# CMD_Light.net
KiCad netlist of a schematic drawn in EAGLE
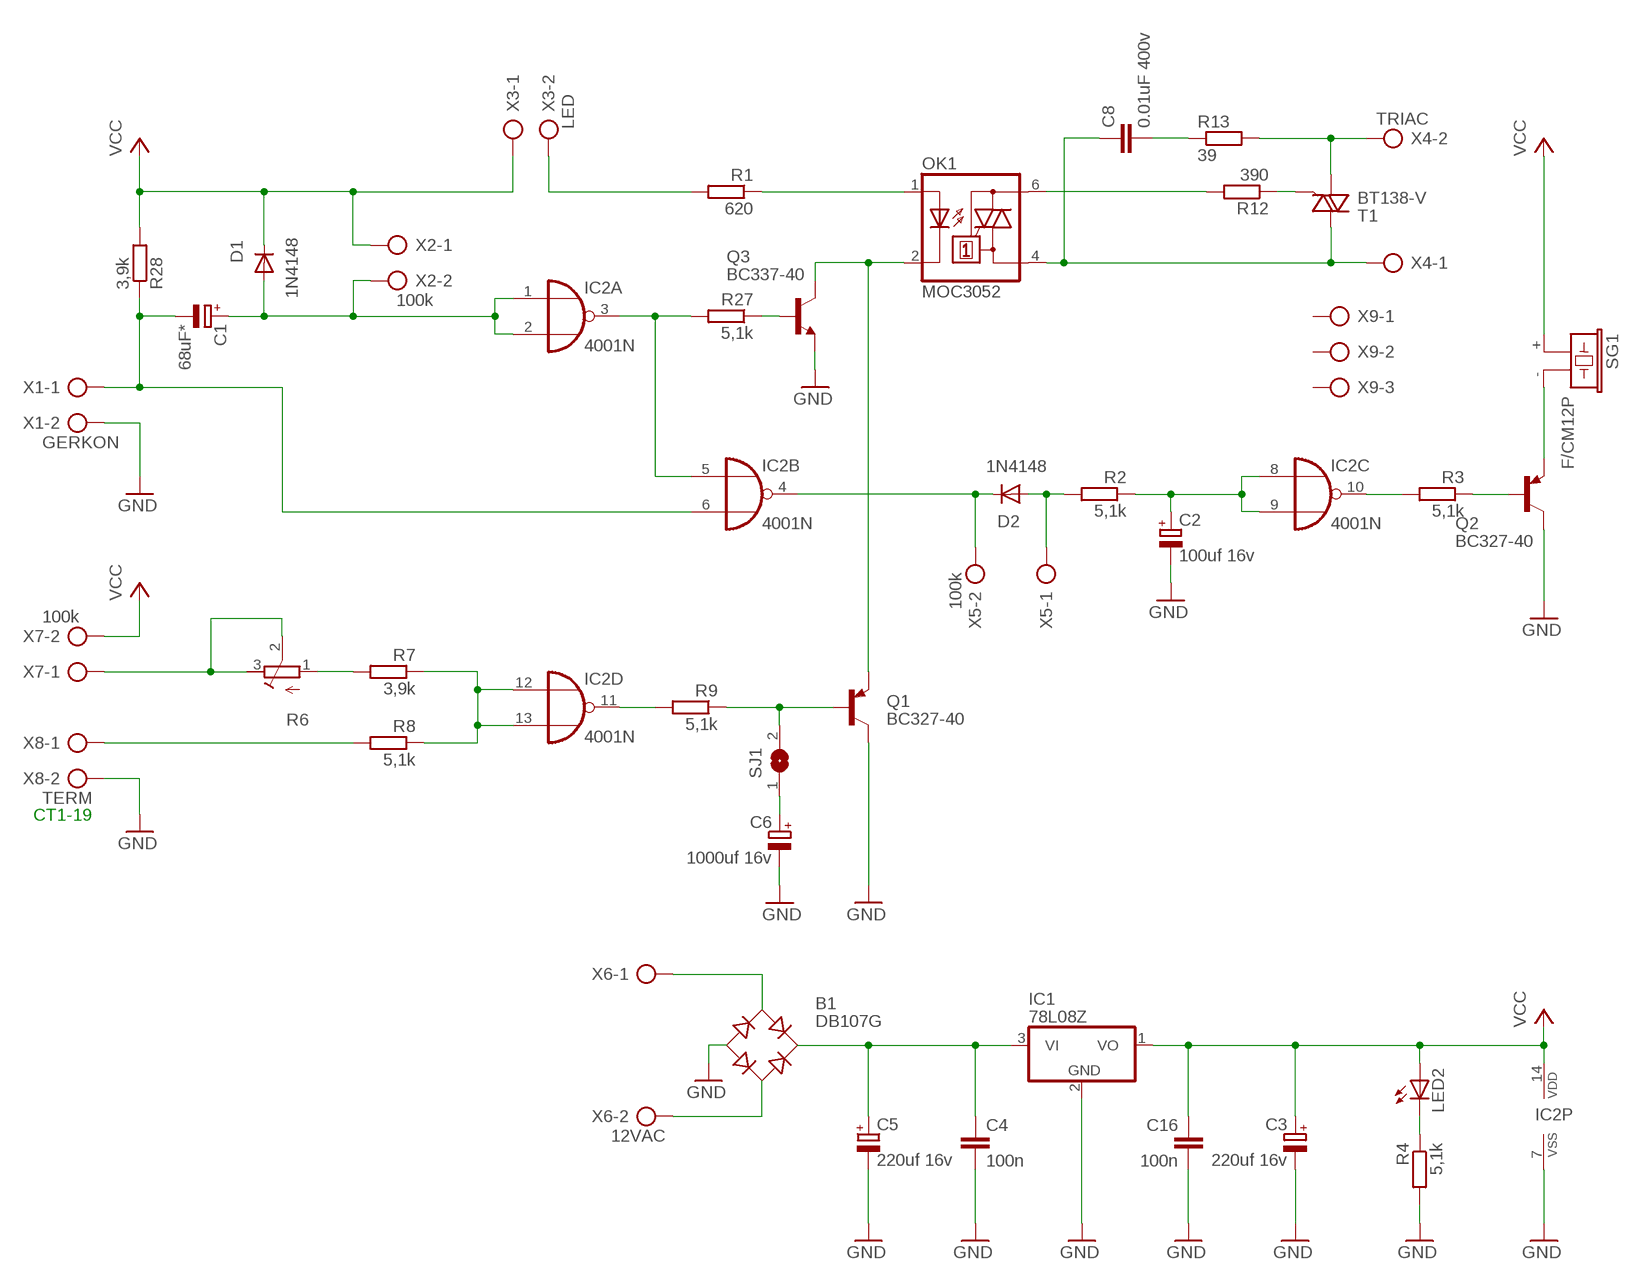
[diagram p0: schematic, sheet 1]

(export (version "E")
  (design (tool "Eeschema 10.0.6"))
  (components
    (comp (ref "B1")
      (value "DB107G")
      (footprint "eagle-import:DB")
      (libsource (lib "eagle-import") (part "DB?GDB107"))
    )
    (comp (ref "C1")
      (value "68uF*")
      (footprint "eagle-import:E3,5-8")
      (libsource (lib "eagle-import") (part "CPOL-EUE3.5-8"))
    )
    (comp (ref "C2")
      (value "100uf 16v")
      (footprint "eagle-import:E3,5-8")
      (libsource (lib "eagle-import") (part "CPOL-EUE3.5-8"))
    )
    (comp (ref "C3")
      (value "220uf 16v")
      (footprint "eagle-import:E3,5-8")
      (libsource (lib "eagle-import") (part "CPOL-EUE3.5-8"))
    )
    (comp (ref "C4")
      (value "100n")
      (footprint "eagle-import:C050-035X075")
      (libsource (lib "eagle-import") (part "C-EU050-035X075"))
    )
    (comp (ref "C5")
      (value "220uf 16v")
      (footprint "eagle-import:E3,5-8")
      (libsource (lib "eagle-import") (part "CPOL-EUE3.5-8"))
    )
    (comp (ref "C6")
      (value "1000uf 16v")
      (footprint "eagle-import:E5-10,5")
      (libsource (lib "eagle-import") (part "CPOL-EUE5-10.5"))
    )
    (comp (ref "C8")
      (value "0.01uF 400v")
      (footprint "eagle-import:C075-063X106")
      (libsource (lib "eagle-import") (part "C-EU075-063X106"))
    )
    (comp (ref "C16")
      (value "100n")
      (footprint "eagle-import:C050-035X075")
      (libsource (lib "eagle-import") (part "C-EU050-035X075"))
    )
    (comp (ref "D1")
      (value "1N4148")
      (footprint "eagle-import:DO41-8")
      (libsource (lib "eagle-import") (part "1N4004_"))
    )
    (comp (ref "D2")
      (value "1N4148")
      (footprint "eagle-import:DO41-10")
      (libsource (lib "eagle-import") (part "1N4004"))
    )
    (comp (ref "IC1")
      (value "78L08Z")
      (footprint "eagle-import:TO92")
      (libsource (lib "eagle-import") (part "78ZL08"))
    )
    (comp (ref "IC2")
      (value "4001N")
      (footprint "eagle-import:DIL14")
      (libsource (lib "eagle-import") (part "4001N"))
    )
    (comp (ref "LED2")
      (value "LED3MM")
      (footprint "eagle-import:LED3MM")
      (libsource (lib "eagle-import") (part "LED3MM"))
    )
    (comp (ref "OK1")
      (value "MOC3052")
      (footprint "eagle-import:DIL06")
      (fields (field (name "MF") "FAIRCHILD SEMICONDUCTOR") (field (name "MPN") "MOC3042-M"))
      (libsource (lib "eagle-import") (part "MOC3042M"))
    )
    (comp (ref "Q1")
      (value "BC327-40")
      (footprint "eagle-import:TO92-EBC")
      (libsource (lib "eagle-import") (part "BC327-40"))
    )
    (comp (ref "Q2")
      (value "BC327-40")
      (footprint "eagle-import:TO92-EBC")
      (libsource (lib "eagle-import") (part "BC327-40"))
    )
    (comp (ref "Q3")
      (value "BC337-40")
      (footprint "eagle-import:TO92-EBC")
      (libsource (lib "eagle-import") (part "BC338-40"))
    )
    (comp (ref "R1")
      (value "620")
      (footprint "eagle-import:0207_10")
      (libsource (lib "eagle-import") (part "R-EU_0207/10"))
    )
    (comp (ref "R2")
      (value "5,1k")
      (footprint "eagle-import:0207_10")
      (libsource (lib "eagle-import") (part "R-EU_0207/10"))
    )
    (comp (ref "R3")
      (value "5,1k")
      (footprint "eagle-import:0207_10")
      (libsource (lib "eagle-import") (part "R-EU_0207/10"))
    )
    (comp (ref "R4")
      (value "5,1k")
      (footprint "eagle-import:0207_10")
      (libsource (lib "eagle-import") (part "R-EU_0207/10"))
    )
    (comp (ref "R6")
      (value "R-TRIMM3339P")
      (footprint "eagle-import:RTRIM3339P")
      (libsource (lib "eagle-import") (part "R-TRIMM3339P"))
    )
    (comp (ref "R7")
      (value "3,9k")
      (footprint "eagle-import:0207_10")
      (libsource (lib "eagle-import") (part "R-EU_0207/10"))
    )
    (comp (ref "R8")
      (value "5,1k")
      (footprint "eagle-import:0207_10")
      (libsource (lib "eagle-import") (part "R-EU_0207/10"))
    )
    (comp (ref "R9")
      (value "5,1k")
      (footprint "eagle-import:0207_10")
      (libsource (lib "eagle-import") (part "R-EU_0207/10"))
    )
    (comp (ref "R12")
      (value "390")
      (footprint "eagle-import:0207_10")
      (libsource (lib "eagle-import") (part "R-EU_0207/10"))
    )
    (comp (ref "R13")
      (value "39")
      (footprint "eagle-import:0411_12")
      (libsource (lib "eagle-import") (part "R-EU_0411/12"))
    )
    (comp (ref "R27")
      (value "5,1k")
      (footprint "eagle-import:0207_10")
      (libsource (lib "eagle-import") (part "R-EU_0207/10"))
    )
    (comp (ref "R28")
      (value "3,9k")
      (footprint "eagle-import:0207_12")
      (libsource (lib "eagle-import") (part "R-EU_0207/12"))
    )
    (comp (ref "SG1")
      (value "F/CM12P")
      (footprint "eagle-import:F_CM12P")
      (libsource (lib "eagle-import") (part "F/CM12P"))
    )
    (comp (ref "SJ1") (value "SJ") (footprint "eagle-import:SJ") (libsource (lib "eagle-import") (part "SJ")))
    (comp (ref "T1")
      (value "BT138-V")
      (footprint "eagle-import:TO220BV")
      (libsource (lib "eagle-import") (part "BT138-V"))
    )
    (comp (ref "X1")
      (value "GERKON")
      (footprint "eagle-import:AK500_2")
      (libsource (lib "eagle-import") (part "AK500/2"))
    )
    (comp (ref "X2")
      (value "100k")
      (footprint "eagle-import:AK500_2")
      (libsource (lib "eagle-import") (part "AK500/2"))
    )
    (comp (ref "X3")
      (value "LED")
      (footprint "eagle-import:AK500_2")
      (libsource (lib "eagle-import") (part "AK500/2"))
    )
    (comp (ref "X4")
      (value "TRIAC")
      (footprint "eagle-import:AK500_2")
      (libsource (lib "eagle-import") (part "AK500/2"))
    )
    (comp (ref "X5")
      (value "100k")
      (footprint "eagle-import:AK500_2")
      (libsource (lib "eagle-import") (part "AK500/2"))
    )
    (comp (ref "X6")
      (value "12VAC")
      (footprint "eagle-import:AK500_2")
      (libsource (lib "eagle-import") (part "AK500/2"))
    )
    (comp (ref "X7")
      (value "100k")
      (footprint "eagle-import:AK500_2")
      (libsource (lib "eagle-import") (part "AK500/2"))
    )
    (comp (ref "X8")
      (value "TERM")
      (footprint "eagle-import:AK500_2")
      (libsource (lib "eagle-import") (part "AK500/2"))
    )
    (comp (ref "X9")
      (value "AK500/3")
      (footprint "eagle-import:AK500_3")
      (libsource (lib "eagle-import") (part "AK500/3"))
    )
  )
  (nets
    (net (code "1") (name "GND") (class "Default")
      (node (ref "B1") (pin "-") (pinfunction "-_-") (pintype "passive"))
      (node (ref "C16") (pin "2") (pinfunction "2_2") (pintype "passive"))
      (node (ref "C2") (pin "-") (pinfunction "-_-") (pintype "passive"))
      (node (ref "C3") (pin "-") (pinfunction "-_-") (pintype "passive"))
      (node (ref "C4") (pin "2") (pinfunction "2_2") (pintype "passive"))
      (node (ref "C5") (pin "-") (pinfunction "-_-") (pintype "passive"))
      (node (ref "C6") (pin "-") (pinfunction "-_-") (pintype "passive"))
      (node (ref "IC1") (pin "2") (pinfunction "GND_2") (pintype "passive"))
      (node (ref "IC2") (pin "7") (pinfunction "VSS_7") (pintype "power_in"))
      (node (ref "Q1") (pin "C") (pinfunction "C_C") (pintype "passive"))
      (node (ref "Q2") (pin "C") (pinfunction "C_C") (pintype "passive"))
      (node (ref "Q3") (pin "E") (pinfunction "E_E") (pintype "passive"))
      (node (ref "R4") (pin "2") (pinfunction "2_2") (pintype "passive"))
      (node (ref "X1") (pin "2") (pinfunction "KL_2") (pintype "passive"))
      (node (ref "X8") (pin "2") (pinfunction "KL_2") (pintype "passive"))
    )
    (net (code "2") (name "Net-(C6-Pad+)") (class "Default")
      (node (ref "C6") (pin "+") (pinfunction "+_+") (pintype "passive"))
      (node (ref "SJ1") (pin "1") (pinfunction "1_1") (pintype "passive"))
    )
    (net (code "3") (name "Net-(C8-Pad2)") (class "Default")
      (node (ref "C8") (pin "2") (pinfunction "2_2") (pintype "passive"))
      (node (ref "R13") (pin "1") (pinfunction "1_1") (pintype "passive"))
    )
    (net (code "4") (name "Net-(IC1-VI)") (class "Default")
      (node (ref "B1") (pin "+") (pinfunction "+_+") (pintype "passive"))
      (node (ref "C4") (pin "1") (pinfunction "1_1") (pintype "passive"))
      (node (ref "C5") (pin "+") (pinfunction "+_+") (pintype "passive"))
      (node (ref "IC1") (pin "3") (pinfunction "VI_3") (pintype "input"))
    )
    (net (code "5") (name "Net-(IC2A-I0)") (class "Default")
      (node (ref "C1") (pin "+") (pinfunction "+_+") (pintype "passive"))
      (node (ref "D1") (pin "A") (pinfunction "A_A") (pintype "passive"))
      (node (ref "IC2") (pin "1") (pinfunction "I0_1") (pintype "input"))
      (node (ref "IC2") (pin "2") (pinfunction "I1_2") (pintype "input"))
      (node (ref "X2") (pin "2") (pinfunction "KL_2") (pintype "passive"))
    )
    (net (code "6") (name "Net-(IC2A-O)") (class "Default")
      (node (ref "IC2") (pin "3") (pinfunction "O_3") (pintype "output"))
      (node (ref "IC2") (pin "5") (pinfunction "I0_5") (pintype "input"))
      (node (ref "R27") (pin "2") (pinfunction "2_2") (pintype "passive"))
    )
    (net (code "7") (name "Net-(IC2B-I1)") (class "Default")
      (node (ref "C1") (pin "-") (pinfunction "-_-") (pintype "passive"))
      (node (ref "IC2") (pin "6") (pinfunction "I1_6") (pintype "input"))
      (node (ref "R28") (pin "1") (pinfunction "1_1") (pintype "passive"))
      (node (ref "X1") (pin "1") (pinfunction "KL_1") (pintype "passive"))
    )
    (net (code "8") (name "Net-(IC2B-O)") (class "Default")
      (node (ref "D2") (pin "C") (pinfunction "C_C") (pintype "passive"))
      (node (ref "IC2") (pin "4") (pinfunction "O_4") (pintype "output"))
      (node (ref "X5") (pin "2") (pinfunction "KL_2") (pintype "passive"))
    )
    (net (code "9") (name "Net-(IC2C-I0)") (class "Default")
      (node (ref "C2") (pin "+") (pinfunction "+_+") (pintype "passive"))
      (node (ref "IC2") (pin "8") (pinfunction "I0_8") (pintype "input"))
      (node (ref "IC2") (pin "9") (pinfunction "I1_9") (pintype "input"))
      (node (ref "R2") (pin "1") (pinfunction "1_1") (pintype "passive"))
    )
    (net (code "10") (name "Net-(IC2C-O)") (class "Default")
      (node (ref "IC2") (pin "10") (pinfunction "O_10") (pintype "output"))
      (node (ref "R3") (pin "2") (pinfunction "2_2") (pintype "passive"))
    )
    (net (code "11") (name "Net-(IC2D-I0)") (class "Default")
      (node (ref "IC2") (pin "12") (pinfunction "I0_12") (pintype "input"))
      (node (ref "IC2") (pin "13") (pinfunction "I1_13") (pintype "input"))
      (node (ref "R7") (pin "1") (pinfunction "1_1") (pintype "passive"))
      (node (ref "R8") (pin "1") (pinfunction "1_1") (pintype "passive"))
    )
    (net (code "12") (name "Net-(IC2D-O)") (class "Default")
      (node (ref "IC2") (pin "11") (pinfunction "O_11") (pintype "output"))
      (node (ref "R9") (pin "2") (pinfunction "2_2") (pintype "passive"))
    )
    (net (code "13") (name "Net-(LED2-C)") (class "Default")
      (node (ref "LED2") (pin "K") (pinfunction "C_K") (pintype "passive"))
      (node (ref "R4") (pin "1") (pinfunction "1_1") (pintype "passive"))
    )
    (net (code "14") (name "Net-(OK1-A)") (class "Default")
      (node (ref "OK1") (pin "1") (pinfunction "A_1") (pintype "passive"))
      (node (ref "R1") (pin "1") (pinfunction "1_1") (pintype "passive"))
    )
    (net (code "15") (name "Net-(OK1-A1)") (class "Default")
      (node (ref "C8") (pin "1") (pinfunction "1_1") (pintype "passive"))
      (node (ref "OK1") (pin "4") (pinfunction "A1_4") (pintype "passive"))
      (node (ref "T1") (pin "T2") (pinfunction "A2_T2") (pintype "passive"))
      (node (ref "X4") (pin "1") (pinfunction "KL_1") (pintype "passive"))
    )
    (net (code "16") (name "Net-(OK1-A2)") (class "Default")
      (node (ref "OK1") (pin "6") (pinfunction "A2_6") (pintype "passive"))
      (node (ref "R12") (pin "2") (pinfunction "2_2") (pintype "passive"))
    )
    (net (code "17") (name "Net-(OK1-C)") (class "Default")
      (node (ref "OK1") (pin "2") (pinfunction "C_2") (pintype "passive"))
      (node (ref "Q1") (pin "E") (pinfunction "E_E") (pintype "passive"))
      (node (ref "Q3") (pin "C") (pinfunction "C_C") (pintype "passive"))
    )
    (net (code "18") (name "Net-(Q1-PadB)") (class "Default")
      (node (ref "Q1") (pin "B") (pinfunction "B_B") (pintype "passive"))
      (node (ref "R9") (pin "1") (pinfunction "1_1") (pintype "passive"))
      (node (ref "SJ1") (pin "2") (pinfunction "2_2") (pintype "passive"))
    )
    (net (code "19") (name "Net-(Q2-PadB)") (class "Default")
      (node (ref "Q2") (pin "B") (pinfunction "B_B") (pintype "passive"))
      (node (ref "R3") (pin "1") (pinfunction "1_1") (pintype "passive"))
    )
    (net (code "20") (name "Net-(Q3-PadB)") (class "Default")
      (node (ref "Q3") (pin "B") (pinfunction "B_B") (pintype "passive"))
      (node (ref "R27") (pin "1") (pinfunction "1_1") (pintype "passive"))
    )
    (net (code "21") (name "Net-(R6-A)") (class "Default")
      (node (ref "R6") (pin "1") (pinfunction "A_1") (pintype "passive"))
      (node (ref "R7") (pin "2") (pinfunction "2_2") (pintype "passive"))
    )
    (net (code "22") (name "Net-(R6-E)") (class "Default")
      (node (ref "R6") (pin "2") (pinfunction "S_2") (pintype "passive"))
      (node (ref "R6") (pin "3") (pinfunction "E_3") (pintype "passive"))
      (node (ref "X7") (pin "1") (pinfunction "KL_1") (pintype "passive"))
    )
    (net (code "23") (name "Net-(R12-Pad1)") (class "Default")
      (node (ref "R12") (pin "1") (pinfunction "1_1") (pintype "passive"))
      (node (ref "T1") (pin "G") (pinfunction "G_G") (pintype "passive"))
    )
    (net (code "24") (name "Net-(SG1-2)") (class "Default")
      (node (ref "Q2") (pin "E") (pinfunction "E_E") (pintype "passive"))
      (node (ref "SG1") (pin "-") (pinfunction "2_-") (pintype "passive"))
    )
    (net (code "25") (name "Net-(T1-A1)") (class "Default")
      (node (ref "R13") (pin "2") (pinfunction "2_2") (pintype "passive"))
      (node (ref "T1") (pin "T1") (pinfunction "A1_T1") (pintype "passive"))
      (node (ref "X4") (pin "2") (pinfunction "KL_2") (pintype "passive"))
    )
    (net (code "26") (name "Net-(X3B-KL)") (class "Default")
      (node (ref "R1") (pin "2") (pinfunction "2_2") (pintype "passive"))
      (node (ref "X3") (pin "2") (pinfunction "KL_2") (pintype "passive"))
    )
    (net (code "27") (name "Net-(X5A-KL)") (class "Default")
      (node (ref "D2") (pin "A") (pinfunction "A_A") (pintype "passive"))
      (node (ref "R2") (pin "2") (pinfunction "2_2") (pintype "passive"))
      (node (ref "X5") (pin "1") (pinfunction "KL_1") (pintype "passive"))
    )
    (net (code "28") (name "Net-(X6A-KL)") (class "Default")
      (node (ref "B1") (pin "AC1") (pinfunction "AC1_AC1") (pintype "passive"))
      (node (ref "X6") (pin "1") (pinfunction "KL_1") (pintype "passive"))
    )
    (net (code "29") (name "Net-(X6B-KL)") (class "Default")
      (node (ref "B1") (pin "AC2") (pinfunction "AC2_AC2") (pintype "passive"))
      (node (ref "X6") (pin "2") (pinfunction "KL_2") (pintype "passive"))
    )
    (net (code "30") (name "Net-(X8A-KL)") (class "Default")
      (node (ref "R8") (pin "2") (pinfunction "2_2") (pintype "passive"))
      (node (ref "X8") (pin "1") (pinfunction "KL_1") (pintype "passive"))
    )
    (net (code "31") (name "VCC") (class "Default")
      (node (ref "C16") (pin "1") (pinfunction "1_1") (pintype "passive"))
      (node (ref "C3") (pin "+") (pinfunction "+_+") (pintype "passive"))
      (node (ref "D1") (pin "C") (pinfunction "C_C") (pintype "passive"))
      (node (ref "IC1") (pin "1") (pinfunction "VO_1") (pintype "passive"))
      (node (ref "IC2") (pin "14") (pinfunction "VDD_14") (pintype "power_in"))
      (node (ref "LED2") (pin "A") (pinfunction "A_A") (pintype "passive"))
      (node (ref "R28") (pin "2") (pinfunction "2_2") (pintype "passive"))
      (node (ref "SG1") (pin "+") (pinfunction "1_+") (pintype "passive"))
      (node (ref "X2") (pin "1") (pinfunction "KL_1") (pintype "passive"))
      (node (ref "X3") (pin "1") (pinfunction "KL_1") (pintype "passive"))
      (node (ref "X7") (pin "2") (pinfunction "KL_2") (pintype "passive"))
    )
    (net (code "32") (name "unconnected-(X9A-KL-Pad1)") (class "Default")
      (node (ref "X9") (pin "1") (pinfunction "KL_1") (pintype "passive"))
    )
    (net (code "33") (name "unconnected-(X9B-KL-Pad2)") (class "Default")
      (node (ref "X9") (pin "2") (pinfunction "KL_2") (pintype "passive"))
    )
    (net (code "34") (name "unconnected-(X9C-KL-Pad3)") (class "Default")
      (node (ref "X9") (pin "3") (pinfunction "KL_3") (pintype "passive"))
    )
  )
)
